# Crimson_rev2.net
KiCad netlist of a schematic drawn in EAGLE
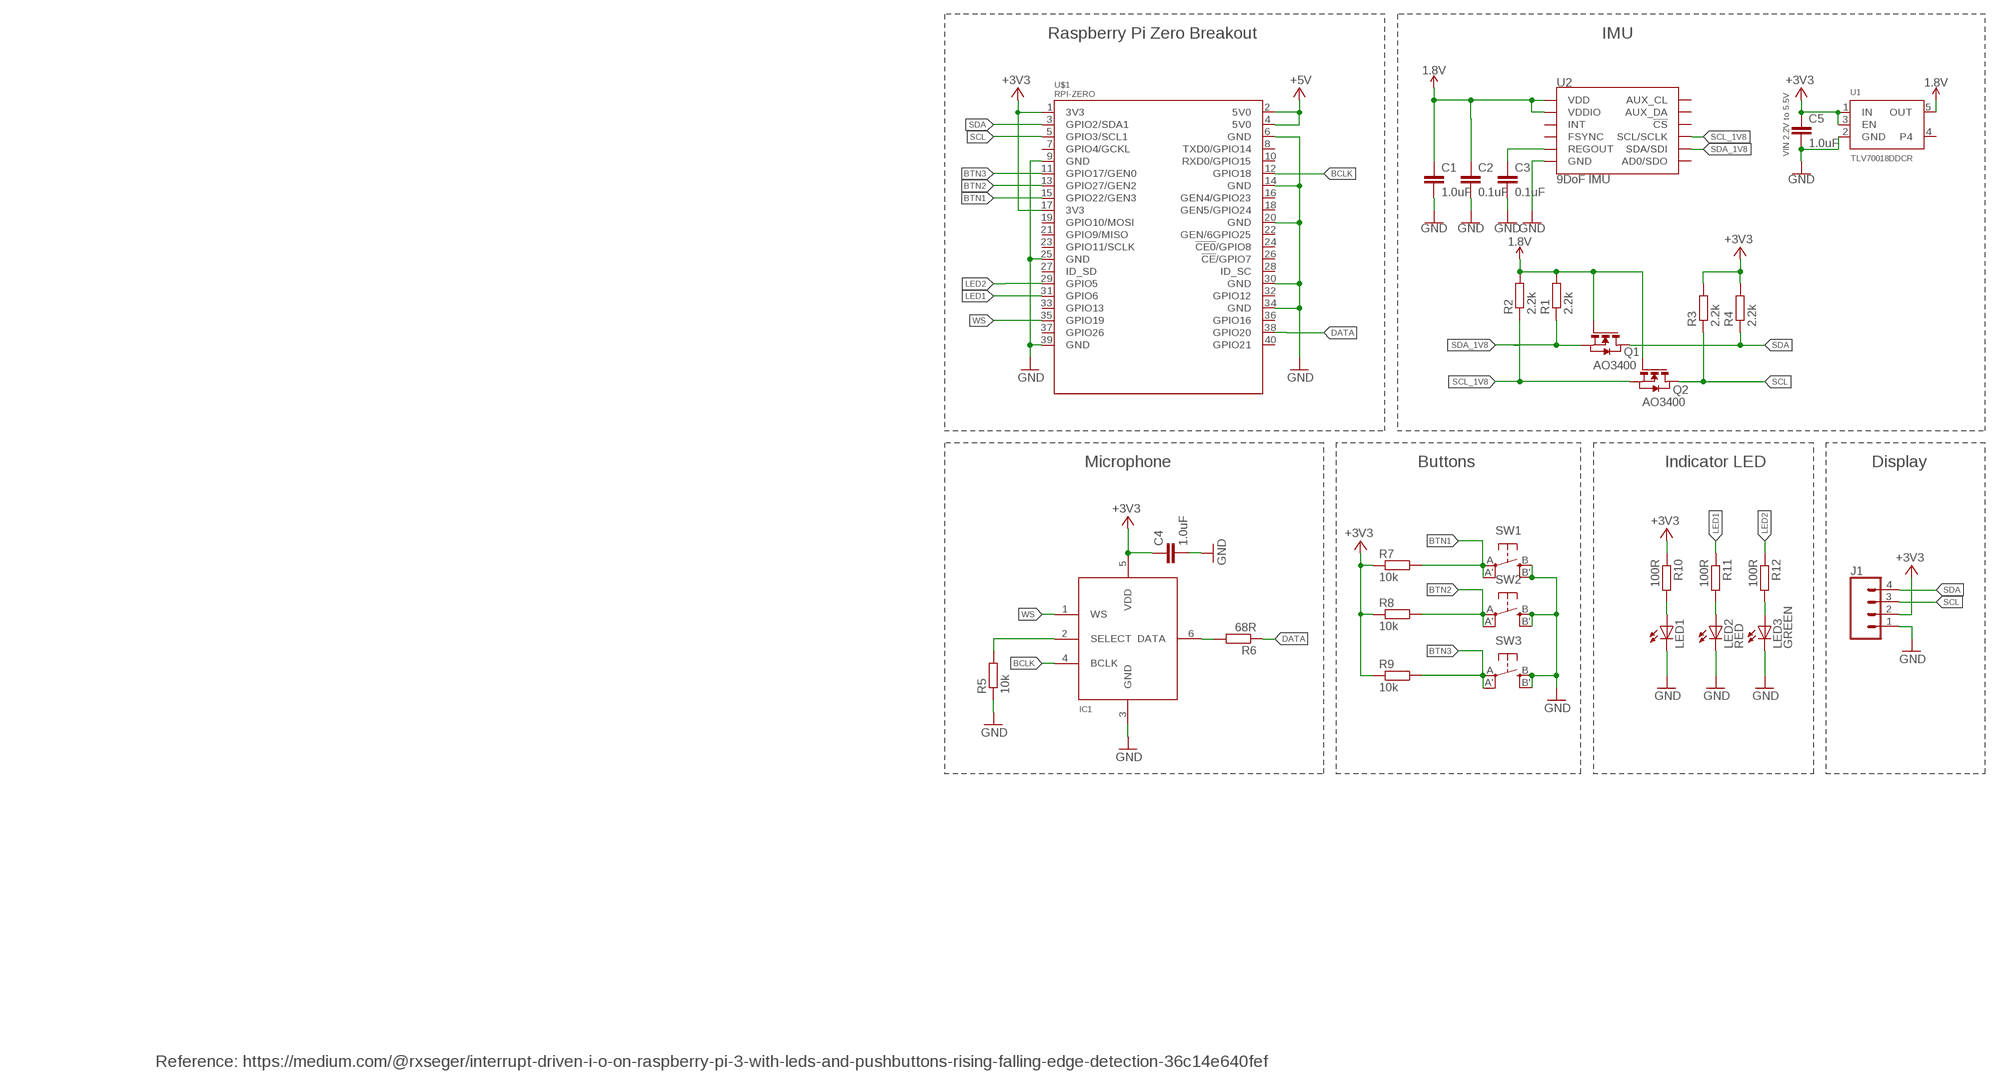
[diagram p0: schematic, sheet 1]

(export (version "E")
  (design (tool "Eeschema 10.0.6"))
  (components
    (comp (ref "C1")
      (value "1.0uF")
      (footprint "eagle-import:0402")
      (libsource (lib "eagle-import") (part "1.0UF-0402-16V-10%"))
    )
    (comp (ref "C2")
      (value "0.1uF")
      (footprint "eagle-import:0402")
      (libsource (lib "eagle-import") (part "0.1UF-0402-16V-10%"))
    )
    (comp (ref "C3")
      (value "0.1uF")
      (footprint "eagle-import:0402")
      (libsource (lib "eagle-import") (part "0.1UF-0402-16V-10%"))
    )
    (comp (ref "C4")
      (value "1.0uF")
      (footprint "eagle-import:0402")
      (libsource (lib "eagle-import") (part "1.0UF-0402-16V-10%"))
    )
    (comp (ref "C5")
      (value "1.0uF")
      (footprint "eagle-import:0402")
      (libsource (lib "eagle-import") (part "1.0UF-0402-16V-10%"))
    )
    (comp (ref "IC1")
      (value "MIC_I2S_SPH0645")
      (footprint "eagle-import:SPH0645LM4H")
      (libsource (lib "eagle-import") (part "MIC_I2S_SPH0645"))
    )
    (comp (ref "J1")
      (value "CONN_04")
      (footprint "eagle-import:1X04")
      (libsource (lib "eagle-import") (part "CONN_04"))
    )
    (comp (ref "LED1")
      (value "LEDCHIPLED_0603")
      (footprint "eagle-import:CHIPLED_0603")
      (libsource (lib "eagle-import") (part "LEDCHIPLED_0603"))
    )
    (comp (ref "LED2")
      (value "RED")
      (footprint "eagle-import:CHIPLED_0603")
      (libsource (lib "eagle-import") (part "LEDCHIPLED_0603"))
    )
    (comp (ref "LED3")
      (value "GREEN")
      (footprint "eagle-import:CHIPLED_0603")
      (libsource (lib "eagle-import") (part "LEDCHIPLED_0603"))
    )
    (comp (ref "Q1")
      (value "AO3400")
      (footprint "eagle-import:SOT-23")
      (libsource (lib "eagle-import") (part "NMOS-SOT23"))
    )
    (comp (ref "Q2")
      (value "AO3400")
      (footprint "eagle-import:SOT-23")
      (libsource (lib "eagle-import") (part "NMOS-SOT23"))
    )
    (comp (ref "R1")
      (value "2.2k")
      (footprint "eagle-import:R0402")
      (libsource (lib "eagle-import") (part "R-EU_R0402"))
    )
    (comp (ref "R2")
      (value "2.2k")
      (footprint "eagle-import:R0402")
      (libsource (lib "eagle-import") (part "R-EU_R0402"))
    )
    (comp (ref "R3")
      (value "2.2k")
      (footprint "eagle-import:R0402")
      (libsource (lib "eagle-import") (part "R-EU_R0402"))
    )
    (comp (ref "R4")
      (value "2.2k")
      (footprint "eagle-import:R0402")
      (libsource (lib "eagle-import") (part "R-EU_R0402"))
    )
    (comp (ref "R5")
      (value "10k")
      (footprint "eagle-import:R0402")
      (libsource (lib "eagle-import") (part "R-EU_R0402"))
    )
    (comp (ref "R6")
      (value "68R")
      (footprint "eagle-import:R0402")
      (libsource (lib "eagle-import") (part "R-EU_R0402"))
    )
    (comp (ref "R7")
      (value "10k")
      (footprint "eagle-import:R0402")
      (libsource (lib "eagle-import") (part "R-EU_R0402"))
    )
    (comp (ref "R8")
      (value "10k")
      (footprint "eagle-import:R0402")
      (libsource (lib "eagle-import") (part "R-EU_R0402"))
    )
    (comp (ref "R9")
      (value "10k")
      (footprint "eagle-import:R0402")
      (libsource (lib "eagle-import") (part "R-EU_R0402"))
    )
    (comp (ref "R10")
      (value "100R")
      (footprint "eagle-import:R0402")
      (libsource (lib "eagle-import") (part "R-EU_R0402"))
    )
    (comp (ref "R11")
      (value "100R")
      (footprint "eagle-import:R0402")
      (libsource (lib "eagle-import") (part "R-EU_R0402"))
    )
    (comp (ref "R12")
      (value "100R")
      (footprint "eagle-import:R0402")
      (libsource (lib "eagle-import") (part "R-EU_R0402"))
    )
    (comp (ref "SW1")
      (value "SPST_TACT-EVQQ2")
      (footprint "eagle-import:EVQ-Q2")
      (libsource (lib "eagle-import") (part "SPST_TACT-EVQQ2"))
    )
    (comp (ref "SW2")
      (value "SPST_TACT-EVQQ2")
      (footprint "eagle-import:EVQ-Q2")
      (libsource (lib "eagle-import") (part "SPST_TACT-EVQQ2"))
    )
    (comp (ref "SW3")
      (value "SPST_TACT-EVQQ2")
      (footprint "eagle-import:EVQ-Q2")
      (libsource (lib "eagle-import") (part "SPST_TACT-EVQQ2"))
    )
    (comp (ref "U$1")
      (value "RPI-ZERO")
      (footprint "eagle-import:RASPBERRYPI_BASTELSTUBE_V13_RASPI_BOARD_B+_FULL")
      (libsource (lib "eagle-import") (part "RPI-ZERO"))
    )
    (comp (ref "U1")
      (value "TLV70018DDCR")
      (footprint "eagle-import:MICROBUILDER_SOT23-5")
      (libsource (lib "eagle-import") (part "MICROBUILDER_VREG_SOT23-5"))
    )
    (comp (ref "U2")
      (value "9DoF IMU")
      (footprint "eagle-import:QFN24-3X3")
      (libsource (lib "eagle-import") (part "ICM-20948"))
    )
  )
  (nets
    (net (code "1") (name "+3V3") (class "Default")
      (node (ref "C4") (pin "1") (pinfunction "1_1") (pintype "passive"))
      (node (ref "C5") (pin "1") (pinfunction "1_1") (pintype "passive"))
      (node (ref "IC1") (pin "5") (pinfunction "VDD_5") (pintype "power_in"))
      (node (ref "J1") (pin "2") (pinfunction "2_2") (pintype "passive"))
      (node (ref "R10") (pin "1") (pinfunction "1_1") (pintype "passive"))
      (node (ref "R3") (pin "2") (pinfunction "2_2") (pintype "passive"))
      (node (ref "R4") (pin "2") (pinfunction "2_2") (pintype "passive"))
      (node (ref "R7") (pin "2") (pinfunction "2_2") (pintype "passive"))
      (node (ref "R8") (pin "2") (pinfunction "2_2") (pintype "passive"))
      (node (ref "R9") (pin "2") (pinfunction "2_2") (pintype "passive"))
      (node (ref "U$1") (pin "1") (pinfunction "3V3_1") (pintype "power_in"))
      (node (ref "U$1") (pin "17") (pinfunction "3V3_17") (pintype "power_in"))
      (node (ref "U1") (pin "1") (pinfunction "IN_1") (pintype "power_in"))
      (node (ref "U1") (pin "3") (pinfunction "EN_3") (pintype "input"))
    )
    (net (code "2") (name "+5V") (class "Default")
      (node (ref "U$1") (pin "2") (pinfunction "5V0_2") (pintype "power_in"))
      (node (ref "U$1") (pin "4") (pinfunction "5V0_4") (pintype "power_in"))
    )
    (net (code "3") (name "1.8V") (class "Default")
      (node (ref "C1") (pin "1") (pinfunction "1_1") (pintype "passive"))
      (node (ref "C2") (pin "1") (pinfunction "1_1") (pintype "passive"))
      (node (ref "Q1") (pin "G") (pinfunction "G_G") (pintype "passive"))
      (node (ref "Q2") (pin "G") (pinfunction "G_G") (pintype "passive"))
      (node (ref "R1") (pin "2") (pinfunction "2_2") (pintype "passive"))
      (node (ref "R2") (pin "2") (pinfunction "2_2") (pintype "passive"))
      (node (ref "U1") (pin "5") (pinfunction "OUT_5") (pintype "power_in"))
      (node (ref "U2") (pin "13") (pinfunction "VDD_13") (pintype "bidirectional"))
      (node (ref "U2") (pin "8") (pinfunction "VDDIO_8") (pintype "bidirectional"))
    )
    (net (code "4") (name "BCLK") (class "Default")
      (node (ref "IC1") (pin "4") (pinfunction "BCLK_4") (pintype "input"))
      (node (ref "U$1") (pin "12") (pinfunction "GPIO18_12") (pintype "bidirectional"))
    )
    (net (code "5") (name "BTN1") (class "Default")
      (node (ref "R7") (pin "1") (pinfunction "1_1") (pintype "passive"))
      (node (ref "SW1") (pin "A") (pinfunction "P_A") (pintype "passive"))
      (node (ref "SW1") (pin "A'") (pinfunction "P1_A'") (pintype "passive"))
      (node (ref "U$1") (pin "15") (pinfunction "GPIO22/GEN3_15") (pintype "bidirectional"))
    )
    (net (code "6") (name "BTN2") (class "Default")
      (node (ref "R8") (pin "1") (pinfunction "1_1") (pintype "passive"))
      (node (ref "SW2") (pin "A") (pinfunction "P_A") (pintype "passive"))
      (node (ref "SW2") (pin "A'") (pinfunction "P1_A'") (pintype "passive"))
      (node (ref "U$1") (pin "13") (pinfunction "GPIO27/GEN2_13") (pintype "bidirectional"))
    )
    (net (code "7") (name "BTN3") (class "Default")
      (node (ref "R9") (pin "1") (pinfunction "1_1") (pintype "passive"))
      (node (ref "SW3") (pin "A") (pinfunction "P_A") (pintype "passive"))
      (node (ref "SW3") (pin "A'") (pinfunction "P1_A'") (pintype "passive"))
      (node (ref "U$1") (pin "11") (pinfunction "GPIO17/GEN0_11") (pintype "bidirectional"))
    )
    (net (code "8") (name "DATA") (class "Default")
      (node (ref "R6") (pin "1") (pinfunction "1_1") (pintype "passive"))
      (node (ref "U$1") (pin "38") (pinfunction "GPIO20_38") (pintype "bidirectional"))
    )
    (net (code "9") (name "GND") (class "Default")
      (node (ref "C1") (pin "2") (pinfunction "2_2") (pintype "passive"))
      (node (ref "C2") (pin "2") (pinfunction "2_2") (pintype "passive"))
      (node (ref "C3") (pin "2") (pinfunction "2_2") (pintype "passive"))
      (node (ref "C4") (pin "2") (pinfunction "2_2") (pintype "passive"))
      (node (ref "C5") (pin "2") (pinfunction "2_2") (pintype "passive"))
      (node (ref "IC1") (pin "3") (pinfunction "GND_3") (pintype "power_in"))
      (node (ref "J1") (pin "1") (pinfunction "1_1") (pintype "passive"))
      (node (ref "LED1") (pin "C") (pinfunction "C_C") (pintype "passive"))
      (node (ref "LED2") (pin "C") (pinfunction "C_C") (pintype "passive"))
      (node (ref "LED3") (pin "C") (pinfunction "C_C") (pintype "passive"))
      (node (ref "R5") (pin "1") (pinfunction "1_1") (pintype "passive"))
      (node (ref "SW1") (pin "B") (pinfunction "S_B") (pintype "passive"))
      (node (ref "SW1") (pin "B'") (pinfunction "S1_B'") (pintype "passive"))
      (node (ref "SW2") (pin "B") (pinfunction "S_B") (pintype "passive"))
      (node (ref "SW2") (pin "B'") (pinfunction "S1_B'") (pintype "passive"))
      (node (ref "SW3") (pin "B") (pinfunction "S_B") (pintype "passive"))
      (node (ref "SW3") (pin "B'") (pinfunction "S1_B'") (pintype "passive"))
      (node (ref "U$1") (pin "14") (pinfunction "GND_14") (pintype "power_in"))
      (node (ref "U$1") (pin "20") (pinfunction "GND_20") (pintype "power_in"))
      (node (ref "U$1") (pin "25") (pinfunction "GND_25") (pintype "power_in"))
      (node (ref "U$1") (pin "30") (pinfunction "GND_30") (pintype "power_in"))
      (node (ref "U$1") (pin "34") (pinfunction "GND_34") (pintype "power_in"))
      (node (ref "U$1") (pin "39") (pinfunction "GND_39") (pintype "power_in"))
      (node (ref "U$1") (pin "6") (pinfunction "GND_6") (pintype "power_in"))
      (node (ref "U$1") (pin "9") (pinfunction "GND_9") (pintype "power_in"))
      (node (ref "U1") (pin "2") (pinfunction "GND_2") (pintype "power_in"))
      (node (ref "U2") (pin "18") (pinfunction "GND_18") (pintype "bidirectional"))
      (node (ref "U2") (pin "20") (pinfunction "GND_20") (pintype "bidirectional"))
    )
    (net (code "10") (name "LED1") (class "Default")
      (node (ref "R11") (pin "1") (pinfunction "1_1") (pintype "passive"))
      (node (ref "U$1") (pin "31") (pinfunction "GPIO6_31") (pintype "bidirectional"))
    )
    (net (code "11") (name "LED2") (class "Default")
      (node (ref "R12") (pin "1") (pinfunction "1_1") (pintype "passive"))
      (node (ref "U$1") (pin "29") (pinfunction "GPIO5_29") (pintype "bidirectional"))
    )
    (net (code "12") (name "Net-(IC1-DATA)") (class "Default")
      (node (ref "IC1") (pin "6") (pinfunction "DATA_6") (pintype "output"))
      (node (ref "R6") (pin "2") (pinfunction "2_2") (pintype "passive"))
    )
    (net (code "13") (name "Net-(IC1-SELECT)") (class "Default")
      (node (ref "IC1") (pin "2") (pinfunction "SELECT_2") (pintype "input"))
      (node (ref "R5") (pin "2") (pinfunction "2_2") (pintype "passive"))
    )
    (net (code "14") (name "Net-(LED1-PadA)") (class "Default")
      (node (ref "LED1") (pin "A") (pinfunction "A_A") (pintype "passive"))
      (node (ref "R10") (pin "2") (pinfunction "2_2") (pintype "passive"))
    )
    (net (code "15") (name "Net-(LED2-PadA)") (class "Default")
      (node (ref "LED2") (pin "A") (pinfunction "A_A") (pintype "passive"))
      (node (ref "R11") (pin "2") (pinfunction "2_2") (pintype "passive"))
    )
    (net (code "16") (name "Net-(LED3-PadA)") (class "Default")
      (node (ref "LED3") (pin "A") (pinfunction "A_A") (pintype "passive"))
      (node (ref "R12") (pin "2") (pinfunction "2_2") (pintype "passive"))
    )
    (net (code "17") (name "Net-(U2-REGOUT)") (class "Default")
      (node (ref "C3") (pin "1") (pinfunction "1_1") (pintype "passive"))
      (node (ref "U2") (pin "10") (pinfunction "REGOUT_10") (pintype "bidirectional"))
    )
    (net (code "18") (name "SCL") (class "Default")
      (node (ref "J1") (pin "3") (pinfunction "3_3") (pintype "passive"))
      (node (ref "Q2") (pin "D") (pinfunction "D_D") (pintype "passive"))
      (node (ref "R3") (pin "1") (pinfunction "1_1") (pintype "passive"))
      (node (ref "U$1") (pin "5") (pinfunction "GPIO3/SCL1_5") (pintype "bidirectional"))
    )
    (net (code "19") (name "SCL_1V8") (class "Default")
      (node (ref "Q2") (pin "S") (pinfunction "S_S") (pintype "passive"))
      (node (ref "R2") (pin "1") (pinfunction "1_1") (pintype "passive"))
      (node (ref "U2") (pin "23") (pinfunction "SCL/SCLK_23") (pintype "bidirectional"))
    )
    (net (code "20") (name "SDA") (class "Default")
      (node (ref "J1") (pin "4") (pinfunction "4_4") (pintype "passive"))
      (node (ref "Q1") (pin "D") (pinfunction "D_D") (pintype "passive"))
      (node (ref "R4") (pin "1") (pinfunction "1_1") (pintype "passive"))
      (node (ref "U$1") (pin "3") (pinfunction "GPIO2/SDA1_3") (pintype "bidirectional"))
    )
    (net (code "21") (name "SDA_1V8") (class "Default")
      (node (ref "Q1") (pin "S") (pinfunction "S_S") (pintype "passive"))
      (node (ref "R1") (pin "1") (pinfunction "1_1") (pintype "passive"))
      (node (ref "U2") (pin "24") (pinfunction "SDA/SDI_24") (pintype "bidirectional"))
    )
    (net (code "22") (name "WS") (class "Default")
      (node (ref "IC1") (pin "1") (pinfunction "WS_1") (pintype "input"))
      (node (ref "U$1") (pin "35") (pinfunction "GPIO19_35") (pintype "bidirectional"))
    )
    (net (code "23") (name "unconnected-(U$1-GEN4{slash}GPIO23-Pad16)") (class "Default")
      (node (ref "U$1") (pin "16") (pinfunction "GEN4/GPIO23_16") (pintype "bidirectional"))
    )
    (net (code "24") (name "unconnected-(U$1-GEN5{slash}GPIO24-Pad18)") (class "Default")
      (node (ref "U$1") (pin "18") (pinfunction "GEN5/GPIO24_18") (pintype "bidirectional"))
    )
    (net (code "25") (name "unconnected-(U$1-GEN{slash}6GPIO25-Pad22)") (class "Default")
      (node (ref "U$1") (pin "22") (pinfunction "GEN/6GPIO25_22") (pintype "bidirectional"))
    )
    (net (code "26") (name "unconnected-(U$1-GPIO4{slash}GCKL-Pad7)") (class "Default")
      (node (ref "U$1") (pin "7") (pinfunction "GPIO4/GCKL_7") (pintype "bidirectional"))
    )
    (net (code "27") (name "unconnected-(U$1-GPIO9{slash}MISO-Pad21)") (class "Default")
      (node (ref "U$1") (pin "21") (pinfunction "GPIO9/MISO_21") (pintype "bidirectional"))
    )
    (net (code "28") (name "unconnected-(U$1-GPIO10{slash}MOSI-Pad19)") (class "Default")
      (node (ref "U$1") (pin "19") (pinfunction "GPIO10/MOSI_19") (pintype "bidirectional"))
    )
    (net (code "29") (name "unconnected-(U$1-GPIO11{slash}SCLK-Pad23)") (class "Default")
      (node (ref "U$1") (pin "23") (pinfunction "GPIO11/SCLK_23") (pintype "bidirectional"))
    )
    (net (code "30") (name "unconnected-(U$1-GPIO12-Pad32)") (class "Default")
      (node (ref "U$1") (pin "32") (pinfunction "GPIO12_32") (pintype "bidirectional"))
    )
    (net (code "31") (name "unconnected-(U$1-GPIO13-Pad33)") (class "Default")
      (node (ref "U$1") (pin "33") (pinfunction "GPIO13_33") (pintype "bidirectional"))
    )
    (net (code "32") (name "unconnected-(U$1-GPIO16-Pad36)") (class "Default")
      (node (ref "U$1") (pin "36") (pinfunction "GPIO16_36") (pintype "bidirectional"))
    )
    (net (code "33") (name "unconnected-(U$1-GPIO21-Pad40)") (class "Default")
      (node (ref "U$1") (pin "40") (pinfunction "GPIO21_40") (pintype "bidirectional"))
    )
    (net (code "34") (name "unconnected-(U$1-GPIO26-Pad37)") (class "Default")
      (node (ref "U$1") (pin "37") (pinfunction "GPIO26_37") (pintype "bidirectional"))
    )
    (net (code "35") (name "unconnected-(U$1-ID_SC-Pad28)") (class "Default")
      (node (ref "U$1") (pin "28") (pinfunction "ID_SC_28") (pintype "bidirectional"))
    )
    (net (code "36") (name "unconnected-(U$1-ID_SD-Pad27)") (class "Default")
      (node (ref "U$1") (pin "27") (pinfunction "ID_SD_27") (pintype "bidirectional"))
    )
    (net (code "37") (name "unconnected-(U$1-RXD0{slash}GPIO15-Pad10)") (class "Default")
      (node (ref "U$1") (pin "10") (pinfunction "RXD0/GPIO15_10") (pintype "bidirectional"))
    )
    (net (code "38") (name "unconnected-(U$1-TXD0{slash}GPIO14-Pad8)") (class "Default")
      (node (ref "U$1") (pin "8") (pinfunction "TXD0/GPIO14_8") (pintype "bidirectional"))
    )
    (net (code "39") (name "unconnected-(U$1-~{CE0}{slash}GPIO8-Pad24)") (class "Default")
      (node (ref "U$1") (pin "24") (pinfunction "~{CE0}/GPIO8_24") (pintype "bidirectional"))
    )
    (net (code "40") (name "unconnected-(U$1-~{CE}{slash}GPIO7-Pad26)") (class "Default")
      (node (ref "U$1") (pin "26") (pinfunction "~{CE}/GPIO7_26") (pintype "bidirectional"))
    )
    (net (code "41") (name "unconnected-(U1-P4-Pad4)") (class "Default")
      (node (ref "U1") (pin "4") (pinfunction "P4_4") (pintype "bidirectional"))
    )
    (net (code "42") (name "unconnected-(U2-AD0{slash}SDO-Pad9)") (class "Default")
      (node (ref "U2") (pin "9") (pinfunction "AD0/SDO_9") (pintype "bidirectional"))
    )
    (net (code "43") (name "unconnected-(U2-AUX_CL-Pad7)") (class "Default")
      (node (ref "U2") (pin "7") (pinfunction "AUX_CL_7") (pintype "bidirectional"))
    )
    (net (code "44") (name "unconnected-(U2-AUX_DA-Pad21)") (class "Default")
      (node (ref "U2") (pin "21") (pinfunction "AUX_DA_21") (pintype "bidirectional"))
    )
    (net (code "45") (name "unconnected-(U2-FSYNC-Pad11)") (class "Default")
      (node (ref "U2") (pin "11") (pinfunction "FSYNC_11") (pintype "bidirectional"))
    )
    (net (code "46") (name "unconnected-(U2-INT-Pad12)") (class "Default")
      (node (ref "U2") (pin "12") (pinfunction "INT_12") (pintype "bidirectional"))
    )
    (net (code "47") (name "unconnected-(U2-~{CS}-Pad22)") (class "Default")
      (node (ref "U2") (pin "22") (pinfunction "~{CS}_22") (pintype "bidirectional"))
    )
  )
)
